# Bike-Power-PCB.net
KiCad netlist of a schematic drawn in EAGLE
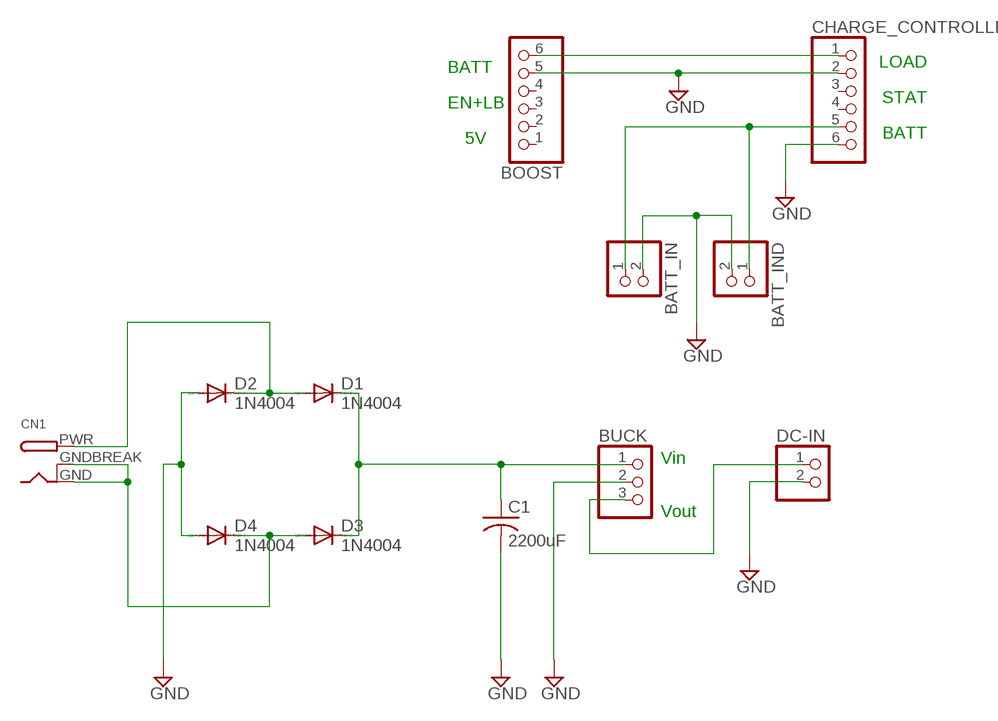
[diagram p0: schematic, sheet 1]

(export (version "E")
  (design (tool "Eeschema 10.0.6"))
  (components
    (comp (ref "BATT_IN")
      (value "JST_2PIN-SMT-RA")
      (footprint "eagle-import:JST-PH-2-SMT-RA")
      (libsource (lib "eagle-import") (part "JST_2PIN-SMT-RA"))
    )
    (comp (ref "BATT_IND")
      (value "PINHD-1X2")
      (footprint "eagle-import:1X02")
      (libsource (lib "eagle-import") (part "PINHD-1X2"))
    )
    (comp (ref "BOOST")
      (value "PINHD-1X6")
      (footprint "eagle-import:1X06")
      (libsource (lib "eagle-import") (part "PINHD-1X6"))
    )
    (comp (ref "BUCK")
      (value "PINHD-1X3")
      (footprint "eagle-import:1X03")
      (libsource (lib "eagle-import") (part "PINHD-1X3"))
    )
    (comp (ref "C1")
      (value "2200uF")
      (footprint "eagle-import:C0805")
      (libsource (lib "eagle-import") (part "C-USC0805"))
    )
    (comp (ref "CHARGE_CONTROLLER")
      (value "PINHD-1X6")
      (footprint "eagle-import:1X06")
      (libsource (lib "eagle-import") (part "PINHD-1X6"))
    )
    (comp (ref "CN1")
      (value "DCBARRELPTH")
      (footprint "eagle-import:DCJACK_2MM_PTH")
      (libsource (lib "eagle-import") (part "DCBARRELPTH"))
    )
    (comp (ref "D1")
      (value "1N4004")
      (footprint "eagle-import:DO41-10")
      (libsource (lib "eagle-import") (part "1N4004"))
    )
    (comp (ref "D2")
      (value "1N4004")
      (footprint "eagle-import:DO41-10")
      (libsource (lib "eagle-import") (part "1N4004"))
    )
    (comp (ref "D3")
      (value "1N4004")
      (footprint "eagle-import:DO41-10")
      (libsource (lib "eagle-import") (part "1N4004"))
    )
    (comp (ref "D4")
      (value "1N4004")
      (footprint "eagle-import:DO41-10")
      (libsource (lib "eagle-import") (part "1N4004"))
    )
    (comp (ref "DC-IN")
      (value "PINHD-1X2")
      (footprint "eagle-import:1X02")
      (libsource (lib "eagle-import") (part "PINHD-1X2"))
    )
  )
  (nets
    (net (code "1") (name "GND") (class "Default")
      (node (ref "BATT_IN") (pin "2") (pinfunction "1_2") (pintype "passive"))
      (node (ref "BATT_IND") (pin "2") (pinfunction "2_2") (pintype "passive"))
      (node (ref "BOOST") (pin "5") (pinfunction "5_5") (pintype "passive"))
      (node (ref "BUCK") (pin "2") (pinfunction "2_2") (pintype "passive"))
      (node (ref "C1") (pin "2") (pinfunction "2_2") (pintype "passive"))
      (node (ref "CHARGE_CONTROLLER") (pin "2") (pinfunction "2_2") (pintype "passive"))
      (node (ref "CHARGE_CONTROLLER") (pin "6") (pinfunction "6_6") (pintype "passive"))
      (node (ref "D2") (pin "A") (pinfunction "A_A") (pintype "passive"))
      (node (ref "D4") (pin "A") (pinfunction "A_A") (pintype "passive"))
      (node (ref "DC-IN") (pin "2") (pinfunction "2_2") (pintype "passive"))
    )
    (net (code "2") (name "Net-(BATT_IN-2)") (class "Default")
      (node (ref "BATT_IN") (pin "1") (pinfunction "2_1") (pintype "passive"))
      (node (ref "BATT_IND") (pin "1") (pinfunction "1_1") (pintype "passive"))
      (node (ref "CHARGE_CONTROLLER") (pin "5") (pinfunction "5_5") (pintype "passive"))
    )
    (net (code "3") (name "Net-(BOOST-Pad6)") (class "Default")
      (node (ref "BOOST") (pin "6") (pinfunction "6_6") (pintype "passive"))
      (node (ref "CHARGE_CONTROLLER") (pin "1") (pinfunction "1_1") (pintype "passive"))
    )
    (net (code "4") (name "Net-(BUCK-Pad1)") (class "Default")
      (node (ref "BUCK") (pin "1") (pinfunction "1_1") (pintype "passive"))
      (node (ref "C1") (pin "1") (pinfunction "1_1") (pintype "passive"))
      (node (ref "D1") (pin "C") (pinfunction "C_C") (pintype "passive"))
      (node (ref "D3") (pin "C") (pinfunction "C_C") (pintype "passive"))
    )
    (net (code "5") (name "Net-(BUCK-Pad3)") (class "Default")
      (node (ref "BUCK") (pin "3") (pinfunction "3_3") (pintype "passive"))
      (node (ref "DC-IN") (pin "1") (pinfunction "1_1") (pintype "passive"))
    )
    (net (code "6") (name "Net-(CN1-PadGND)") (class "Default")
      (node (ref "CN1") (pin "GND") (pinfunction "GND_GND") (pintype "power_in"))
      (node (ref "CN1") (pin "GNDBREAK") (pinfunction "GNDBREAK_GNDBREAK") (pintype "power_in"))
      (node (ref "D3") (pin "A") (pinfunction "A_A") (pintype "passive"))
      (node (ref "D4") (pin "C") (pinfunction "C_C") (pintype "passive"))
    )
    (net (code "7") (name "Net-(CN1-PadPWR)") (class "Default")
      (node (ref "CN1") (pin "PWR") (pinfunction "PWR_PWR") (pintype "power_in"))
      (node (ref "D1") (pin "A") (pinfunction "A_A") (pintype "passive"))
      (node (ref "D2") (pin "C") (pinfunction "C_C") (pintype "passive"))
    )
    (net (code "8") (name "unconnected-(BOOST-Pad1)") (class "Default")
      (node (ref "BOOST") (pin "1") (pinfunction "1_1") (pintype "passive"))
    )
    (net (code "9") (name "unconnected-(BOOST-Pad2)") (class "Default")
      (node (ref "BOOST") (pin "2") (pinfunction "2_2") (pintype "passive"))
    )
    (net (code "10") (name "unconnected-(BOOST-Pad3)") (class "Default")
      (node (ref "BOOST") (pin "3") (pinfunction "3_3") (pintype "passive"))
    )
    (net (code "11") (name "unconnected-(BOOST-Pad4)") (class "Default")
      (node (ref "BOOST") (pin "4") (pinfunction "4_4") (pintype "passive"))
    )
    (net (code "12") (name "unconnected-(CHARGE_CONTROLLER-Pad3)") (class "Default")
      (node (ref "CHARGE_CONTROLLER") (pin "3") (pinfunction "3_3") (pintype "passive"))
    )
    (net (code "13") (name "unconnected-(CHARGE_CONTROLLER-Pad4)") (class "Default")
      (node (ref "CHARGE_CONTROLLER") (pin "4") (pinfunction "4_4") (pintype "passive"))
    )
  )
)
